# Sine_5KW_co_sac_copy.net
KiCad netlist of a schematic drawn in EAGLE
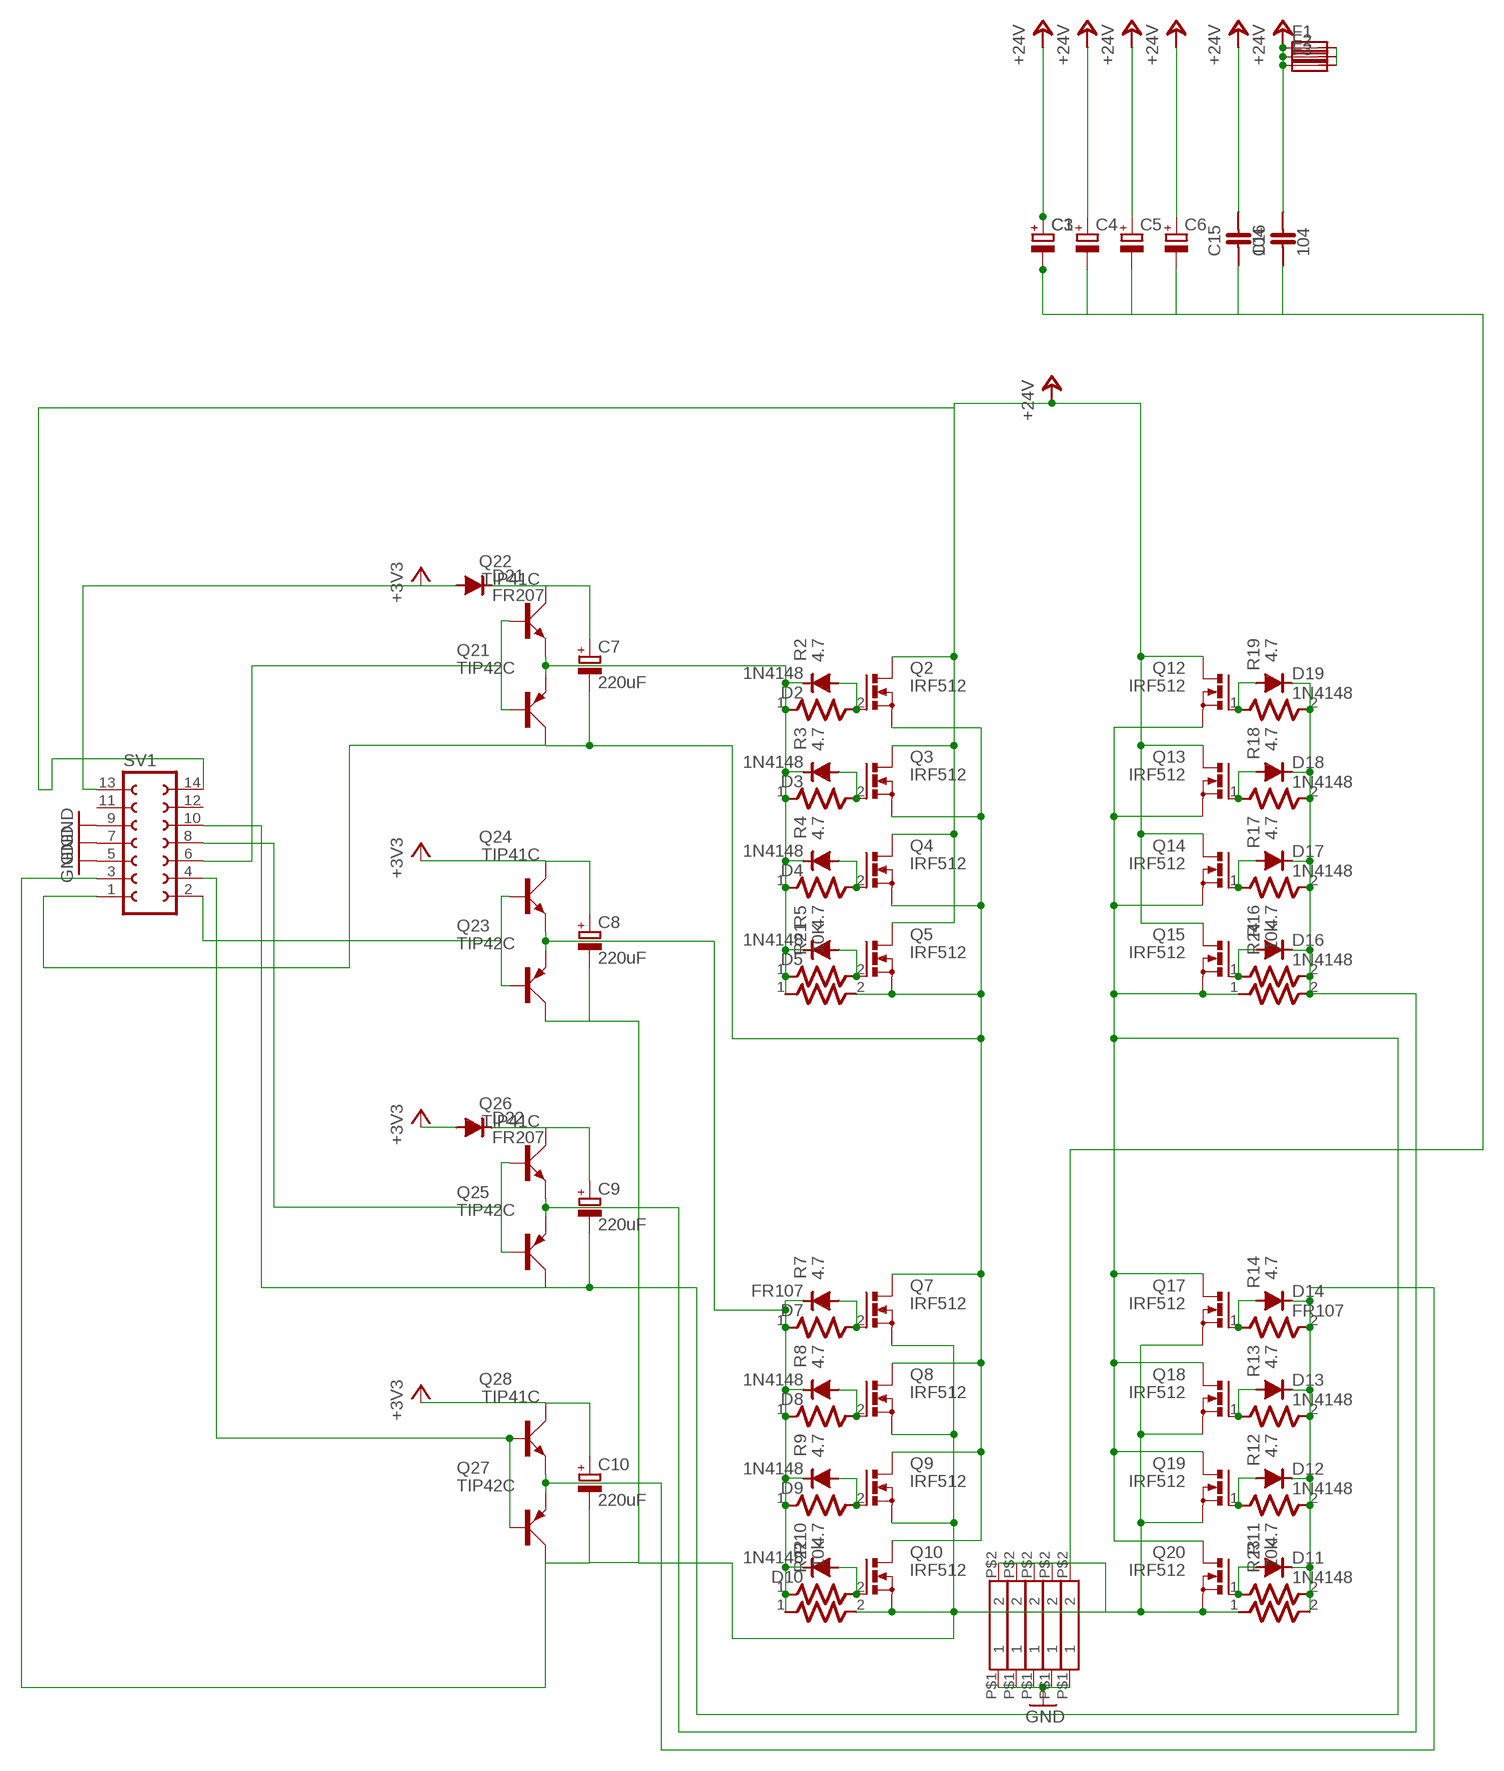
[diagram p0: schematic, sheet 1]

(export (version "E")
  (design (tool "Eeschema 10.0.6"))
  (components
    (comp (ref "C1")
      (value "CPOL-EUE7.5-18")
      (footprint "eagle-import:E7,5-18")
      (libsource (lib "eagle-import") (part "CPOL-EUE7.5-18"))
    )
    (comp (ref "C3")
      (value "CPOL-EUE7.5-18")
      (footprint "eagle-import:E7,5-18")
      (libsource (lib "eagle-import") (part "CPOL-EUE7.5-18"))
    )
    (comp (ref "C4")
      (value "CPOL-EUE7.5-18")
      (footprint "eagle-import:E7,5-18")
      (libsource (lib "eagle-import") (part "CPOL-EUE7.5-18"))
    )
    (comp (ref "C5")
      (value "CPOL-EUE7.5-18")
      (footprint "eagle-import:E7,5-18")
      (libsource (lib "eagle-import") (part "CPOL-EUE7.5-18"))
    )
    (comp (ref "C6")
      (value "CPOL-EUE7.5-18")
      (footprint "eagle-import:E7,5-18")
      (libsource (lib "eagle-import") (part "CPOL-EUE7.5-18"))
    )
    (comp (ref "C7")
      (value "220uF")
      (footprint "eagle-import:E5-8,5")
      (libsource (lib "eagle-import") (part "CPOL-EUE5-8.5"))
    )
    (comp (ref "C8")
      (value "220uF")
      (footprint "eagle-import:E5-8,5")
      (libsource (lib "eagle-import") (part "CPOL-EUE5-8.5"))
    )
    (comp (ref "C9")
      (value "220uF")
      (footprint "eagle-import:E5-8,5")
      (libsource (lib "eagle-import") (part "CPOL-EUE5-8.5"))
    )
    (comp (ref "C10")
      (value "220uF")
      (footprint "eagle-import:E5-8,5")
      (libsource (lib "eagle-import") (part "CPOL-EUE5-8.5"))
    )
    (comp (ref "C15")
      (value "104")
      (footprint "eagle-import:CAP-NP5")
      (libsource (lib "eagle-import") (part "CAP-NP5"))
    )
    (comp (ref "C16")
      (value "104")
      (footprint "eagle-import:CAP-NP5")
      (libsource (lib "eagle-import") (part "CAP-NP5"))
    )
    (comp (ref "D2")
      (value "1N4148")
      (footprint "eagle-import:D-7,5")
      (libsource (lib "eagle-import") (part "1N4148"))
    )
    (comp (ref "D3")
      (value "1N4148")
      (footprint "eagle-import:D-7,5")
      (libsource (lib "eagle-import") (part "1N4148"))
    )
    (comp (ref "D4")
      (value "1N4148")
      (footprint "eagle-import:D-7,5")
      (libsource (lib "eagle-import") (part "1N4148"))
    )
    (comp (ref "D5")
      (value "1N4148")
      (footprint "eagle-import:D-7,5")
      (libsource (lib "eagle-import") (part "1N4148"))
    )
    (comp (ref "D7")
      (value "FR107")
      (footprint "eagle-import:D-7,5")
      (libsource (lib "eagle-import") (part "1N4148"))
    )
    (comp (ref "D8")
      (value "1N4148")
      (footprint "eagle-import:D-7,5")
      (libsource (lib "eagle-import") (part "1N4148"))
    )
    (comp (ref "D9")
      (value "1N4148")
      (footprint "eagle-import:D-7,5")
      (libsource (lib "eagle-import") (part "1N4148"))
    )
    (comp (ref "D10")
      (value "1N4148")
      (footprint "eagle-import:D-7,5")
      (libsource (lib "eagle-import") (part "1N4148"))
    )
    (comp (ref "D11")
      (value "1N4148")
      (footprint "eagle-import:D-7,5")
      (libsource (lib "eagle-import") (part "1N4148"))
    )
    (comp (ref "D12")
      (value "1N4148")
      (footprint "eagle-import:D-7,5")
      (libsource (lib "eagle-import") (part "1N4148"))
    )
    (comp (ref "D13")
      (value "1N4148")
      (footprint "eagle-import:D-7,5")
      (libsource (lib "eagle-import") (part "1N4148"))
    )
    (comp (ref "D14")
      (value "FR107")
      (footprint "eagle-import:D-7,5")
      (libsource (lib "eagle-import") (part "1N4148"))
    )
    (comp (ref "D16")
      (value "1N4148")
      (footprint "eagle-import:D-7,5")
      (libsource (lib "eagle-import") (part "1N4148"))
    )
    (comp (ref "D17")
      (value "1N4148")
      (footprint "eagle-import:D-7,5")
      (libsource (lib "eagle-import") (part "1N4148"))
    )
    (comp (ref "D18")
      (value "1N4148")
      (footprint "eagle-import:D-7,5")
      (libsource (lib "eagle-import") (part "1N4148"))
    )
    (comp (ref "D19")
      (value "1N4148")
      (footprint "eagle-import:D-7,5")
      (libsource (lib "eagle-import") (part "1N4148"))
    )
    (comp (ref "D21")
      (value "FR207")
      (footprint "eagle-import:D-7,5")
      (libsource (lib "eagle-import") (part "1N4148"))
    )
    (comp (ref "D22")
      (value "FR207")
      (footprint "eagle-import:D-7,5")
      (libsource (lib "eagle-import") (part "1N4148"))
    )
    (comp (ref "F1")
      (value "LITTLEFUSE")
      (footprint "eagle-import:LITTLEFUSE")
      (libsource (lib "eagle-import") (part "LITTLEFUSE"))
    )
    (comp (ref "F2")
      (value "LITTLEFUSE")
      (footprint "eagle-import:LITTLEFUSE")
      (libsource (lib "eagle-import") (part "LITTLEFUSE"))
    )
    (comp (ref "F3")
      (value "LITTLEFUSE")
      (footprint "eagle-import:LITTLEFUSE")
      (libsource (lib "eagle-import") (part "LITTLEFUSE"))
    )
    (comp (ref "Q2")
      (value "IRF512")
      (footprint "eagle-import:TO220BV")
      (libsource (lib "eagle-import") (part "IRF512"))
    )
    (comp (ref "Q3")
      (value "IRF512")
      (footprint "eagle-import:TO220BV")
      (libsource (lib "eagle-import") (part "IRF512"))
    )
    (comp (ref "Q4")
      (value "IRF512")
      (footprint "eagle-import:TO220BV")
      (libsource (lib "eagle-import") (part "IRF512"))
    )
    (comp (ref "Q5")
      (value "IRF512")
      (footprint "eagle-import:TO220BV")
      (libsource (lib "eagle-import") (part "IRF512"))
    )
    (comp (ref "Q7")
      (value "IRF512")
      (footprint "eagle-import:TO220BV")
      (libsource (lib "eagle-import") (part "IRF512"))
    )
    (comp (ref "Q8")
      (value "IRF512")
      (footprint "eagle-import:TO220BV")
      (libsource (lib "eagle-import") (part "IRF512"))
    )
    (comp (ref "Q9")
      (value "IRF512")
      (footprint "eagle-import:TO220BV")
      (libsource (lib "eagle-import") (part "IRF512"))
    )
    (comp (ref "Q10")
      (value "IRF512")
      (footprint "eagle-import:TO220BV")
      (libsource (lib "eagle-import") (part "IRF512"))
    )
    (comp (ref "Q12")
      (value "IRF512")
      (footprint "eagle-import:TO220BV")
      (libsource (lib "eagle-import") (part "IRF512"))
    )
    (comp (ref "Q13")
      (value "IRF512")
      (footprint "eagle-import:TO220BV")
      (libsource (lib "eagle-import") (part "IRF512"))
    )
    (comp (ref "Q14")
      (value "IRF512")
      (footprint "eagle-import:TO220BV")
      (fields (field (name "SPICEPREFIX") "M"))
      (libsource (lib "eagle-import") (part "IRF512"))
    )
    (comp (ref "Q15")
      (value "IRF512")
      (footprint "eagle-import:TO220BV")
      (libsource (lib "eagle-import") (part "IRF512"))
    )
    (comp (ref "Q17")
      (value "IRF512")
      (footprint "eagle-import:TO220BV")
      (libsource (lib "eagle-import") (part "IRF512"))
    )
    (comp (ref "Q18")
      (value "IRF512")
      (footprint "eagle-import:TO220BV")
      (libsource (lib "eagle-import") (part "IRF512"))
    )
    (comp (ref "Q19")
      (value "IRF512")
      (footprint "eagle-import:TO220BV")
      (libsource (lib "eagle-import") (part "IRF512"))
    )
    (comp (ref "Q20")
      (value "IRF512")
      (footprint "eagle-import:TO220BV")
      (libsource (lib "eagle-import") (part "IRF512"))
    )
    (comp (ref "Q21")
      (value "TIP42C")
      (footprint "eagle-import:TO220AV")
      (fields (field (name "SPICEPREFIX") "Q"))
      (libsource (lib "eagle-import") (part "TIP42C"))
    )
    (comp (ref "Q22")
      (value "TIP41C")
      (footprint "eagle-import:TO220AV")
      (libsource (lib "eagle-import") (part "TIP41C"))
    )
    (comp (ref "Q23")
      (value "TIP42C")
      (footprint "eagle-import:TO220AV")
      (libsource (lib "eagle-import") (part "TIP42C"))
    )
    (comp (ref "Q24")
      (value "TIP41C")
      (footprint "eagle-import:TO220AV")
      (libsource (lib "eagle-import") (part "TIP41C"))
    )
    (comp (ref "Q25")
      (value "TIP42C")
      (footprint "eagle-import:TO220AV")
      (libsource (lib "eagle-import") (part "TIP42C"))
    )
    (comp (ref "Q26")
      (value "TIP41C")
      (footprint "eagle-import:TO220AV")
      (libsource (lib "eagle-import") (part "TIP41C"))
    )
    (comp (ref "Q27")
      (value "TIP42C")
      (footprint "eagle-import:TO220AV")
      (libsource (lib "eagle-import") (part "TIP42C"))
    )
    (comp (ref "Q28")
      (value "TIP41C")
      (footprint "eagle-import:TO220AV")
      (libsource (lib "eagle-import") (part "TIP41C"))
    )
    (comp (ref "R2")
      (value "4.7")
      (footprint "eagle-import:R-7,5")
      (libsource (lib "eagle-import") (part "R-7,5"))
    )
    (comp (ref "R3")
      (value "4.7")
      (footprint "eagle-import:R-7,5")
      (libsource (lib "eagle-import") (part "R-7,5"))
    )
    (comp (ref "R4")
      (value "4.7")
      (footprint "eagle-import:R-7,5")
      (libsource (lib "eagle-import") (part "R-7,5"))
    )
    (comp (ref "R5")
      (value "4.7")
      (footprint "eagle-import:R-7,5")
      (libsource (lib "eagle-import") (part "R-7,5"))
    )
    (comp (ref "R7")
      (value "4.7")
      (footprint "eagle-import:R-7,5")
      (libsource (lib "eagle-import") (part "R-7,5"))
    )
    (comp (ref "R8")
      (value "4.7")
      (footprint "eagle-import:R-7,5")
      (libsource (lib "eagle-import") (part "R-7,5"))
    )
    (comp (ref "R9")
      (value "4.7")
      (footprint "eagle-import:R-7,5")
      (libsource (lib "eagle-import") (part "R-7,5"))
    )
    (comp (ref "R10")
      (value "4.7")
      (footprint "eagle-import:R-7,5")
      (libsource (lib "eagle-import") (part "R-7,5"))
    )
    (comp (ref "R11")
      (value "4.7")
      (footprint "eagle-import:R-7,5")
      (libsource (lib "eagle-import") (part "R-7,5"))
    )
    (comp (ref "R12")
      (value "4.7")
      (footprint "eagle-import:R-7,5")
      (libsource (lib "eagle-import") (part "R-7,5"))
    )
    (comp (ref "R13")
      (value "4.7")
      (footprint "eagle-import:R-7,5")
      (libsource (lib "eagle-import") (part "R-7,5"))
    )
    (comp (ref "R14")
      (value "4.7")
      (footprint "eagle-import:R-7,5")
      (libsource (lib "eagle-import") (part "R-7,5"))
    )
    (comp (ref "R16")
      (value "4.7")
      (footprint "eagle-import:R-7,5")
      (libsource (lib "eagle-import") (part "R-7,5"))
    )
    (comp (ref "R17")
      (value "4.7")
      (footprint "eagle-import:R-7,5")
      (libsource (lib "eagle-import") (part "R-7,5"))
    )
    (comp (ref "R18")
      (value "4.7")
      (footprint "eagle-import:R-7,5")
      (libsource (lib "eagle-import") (part "R-7,5"))
    )
    (comp (ref "R19")
      (value "4.7")
      (footprint "eagle-import:R-7,5")
      (libsource (lib "eagle-import") (part "R-7,5"))
    )
    (comp (ref "R21")
      (value "10K")
      (footprint "eagle-import:R-7,5")
      (libsource (lib "eagle-import") (part "R-7,5"))
    )
    (comp (ref "R22")
      (value "10k")
      (footprint "eagle-import:R-7,5")
      (libsource (lib "eagle-import") (part "R-7,5"))
    )
    (comp (ref "R23")
      (value "10k")
      (footprint "eagle-import:R-7,5")
      (libsource (lib "eagle-import") (part "R-7,5"))
    )
    (comp (ref "R24")
      (value "10k")
      (footprint "eagle-import:R-7,5")
      (libsource (lib "eagle-import") (part "R-7,5"))
    )
    (comp (ref "SV1")
      (value "FE07-2")
      (footprint "eagle-import:FE07-2")
      (fields (field (name "SPICEPREFIX") "X"))
      (libsource (lib "eagle-import") (part "FE07-2"))
    )
    (comp (ref "U$2")
      (value "SHUNT")
      (footprint "eagle-import:SHUNT")
      (libsource (lib "eagle-import") (part "SHUNT"))
    )
    (comp (ref "U$3")
      (value "SHUNT")
      (footprint "eagle-import:SHUNT")
      (libsource (lib "eagle-import") (part "SHUNT"))
    )
    (comp (ref "U$8")
      (value "SHUNT")
      (footprint "eagle-import:SHUNT")
      (libsource (lib "eagle-import") (part "SHUNT"))
    )
    (comp (ref "U$9")
      (value "SHUNT")
      (footprint "eagle-import:SHUNT")
      (libsource (lib "eagle-import") (part "SHUNT"))
    )
    (comp (ref "U$10")
      (value "SHUNT")
      (footprint "eagle-import:SHUNT")
      (libsource (lib "eagle-import") (part "SHUNT"))
    )
  )
  (nets
    (net (code "1") (name "+3V3") (class "Default")
      (node (ref "C10") (pin "+") (pinfunction "+_+") (pintype "passive"))
      (node (ref "C8") (pin "+") (pinfunction "+_+") (pintype "passive"))
      (node (ref "D21") (pin "A") (pinfunction "A_A") (pintype "passive"))
      (node (ref "D22") (pin "A") (pinfunction "A_A") (pintype "passive"))
      (node (ref "Q24") (pin "C") (pinfunction "C_C") (pintype "passive"))
      (node (ref "Q28") (pin "C") (pinfunction "C_C") (pintype "passive"))
      (node (ref "SV1") (pin "13") (pinfunction "13_13") (pintype "passive"))
    )
    (net (code "2") (name "+24V") (class "Default")
      (node (ref "C1") (pin "+") (pinfunction "+_+") (pintype "passive"))
      (node (ref "C15") (pin "2") (pinfunction "2_2") (pintype "passive"))
      (node (ref "C16") (pin "2") (pinfunction "2_2") (pintype "passive"))
      (node (ref "C3") (pin "+") (pinfunction "+_+") (pintype "passive"))
      (node (ref "C4") (pin "+") (pinfunction "+_+") (pintype "passive"))
      (node (ref "C5") (pin "+") (pinfunction "+_+") (pintype "passive"))
      (node (ref "C6") (pin "+") (pinfunction "+_+") (pintype "passive"))
      (node (ref "F1") (pin "1") (pinfunction "1_1") (pintype "passive"))
      (node (ref "F2") (pin "1") (pinfunction "1_1") (pintype "passive"))
      (node (ref "F3") (pin "1") (pinfunction "1_1") (pintype "passive"))
      (node (ref "Q12") (pin "D") (pinfunction "D_D") (pintype "passive"))
      (node (ref "Q13") (pin "D") (pinfunction "D_D") (pintype "passive"))
      (node (ref "Q14") (pin "D") (pinfunction "D_D") (pintype "passive"))
      (node (ref "Q15") (pin "D") (pinfunction "D_D") (pintype "passive"))
      (node (ref "Q2") (pin "D") (pinfunction "D_D") (pintype "passive"))
      (node (ref "Q3") (pin "D") (pinfunction "D_D") (pintype "passive"))
      (node (ref "Q4") (pin "D") (pinfunction "D_D") (pintype "passive"))
      (node (ref "Q5") (pin "D") (pinfunction "D_D") (pintype "passive"))
      (node (ref "SV1") (pin "14") (pinfunction "14_14") (pintype "passive"))
    )
    (net (code "3") (name "GND") (class "Default")
      (node (ref "SV1") (pin "5") (pinfunction "5_5") (pintype "passive"))
      (node (ref "SV1") (pin "7") (pinfunction "7_7") (pintype "passive"))
      (node (ref "SV1") (pin "9") (pinfunction "9_9") (pintype "passive"))
      (node (ref "U$10") (pin "P$1") (pinfunction "1_P$1") (pintype "bidirectional"))
      (node (ref "U$2") (pin "P$1") (pinfunction "1_P$1") (pintype "bidirectional"))
      (node (ref "U$3") (pin "P$1") (pinfunction "1_P$1") (pintype "bidirectional"))
      (node (ref "U$8") (pin "P$1") (pinfunction "1_P$1") (pintype "bidirectional"))
      (node (ref "U$9") (pin "P$1") (pinfunction "1_P$1") (pintype "bidirectional"))
    )
    (net (code "4") (name "Net-(C7-Pad+)") (class "Default")
      (node (ref "C7") (pin "+") (pinfunction "+_+") (pintype "passive"))
      (node (ref "D21") (pin "C") (pinfunction "C_C") (pintype "passive"))
      (node (ref "Q22") (pin "C") (pinfunction "C_C") (pintype "passive"))
    )
    (net (code "5") (name "Net-(C7-Pad-)") (class "Default")
      (node (ref "C7") (pin "-") (pinfunction "-_-") (pintype "passive"))
      (node (ref "Q10") (pin "D") (pinfunction "D_D") (pintype "passive"))
      (node (ref "Q2") (pin "S") (pinfunction "S_S") (pintype "passive"))
      (node (ref "Q21") (pin "C") (pinfunction "C_C") (pintype "passive"))
      (node (ref "Q3") (pin "S") (pinfunction "S_S") (pintype "passive"))
      (node (ref "Q4") (pin "S") (pinfunction "S_S") (pintype "passive"))
      (node (ref "Q5") (pin "S") (pinfunction "S_S") (pintype "passive"))
      (node (ref "Q7") (pin "D") (pinfunction "D_D") (pintype "passive"))
      (node (ref "Q8") (pin "D") (pinfunction "D_D") (pintype "passive"))
      (node (ref "Q9") (pin "D") (pinfunction "D_D") (pintype "passive"))
      (node (ref "R21") (pin "2") (pinfunction "2_2") (pintype "passive"))
      (node (ref "SV1") (pin "1") (pinfunction "1_1") (pintype "passive"))
    )
    (net (code "6") (name "Net-(C9-Pad+)") (class "Default")
      (node (ref "C9") (pin "+") (pinfunction "+_+") (pintype "passive"))
      (node (ref "D22") (pin "C") (pinfunction "C_C") (pintype "passive"))
      (node (ref "Q26") (pin "C") (pinfunction "C_C") (pintype "passive"))
    )
    (net (code "7") (name "Net-(C9-Pad-)") (class "Default")
      (node (ref "C9") (pin "-") (pinfunction "-_-") (pintype "passive"))
      (node (ref "Q12") (pin "S") (pinfunction "S_S") (pintype "passive"))
      (node (ref "Q13") (pin "S") (pinfunction "S_S") (pintype "passive"))
      (node (ref "Q14") (pin "S") (pinfunction "S_S") (pintype "passive"))
      (node (ref "Q15") (pin "S") (pinfunction "S_S") (pintype "passive"))
      (node (ref "Q17") (pin "D") (pinfunction "D_D") (pintype "passive"))
      (node (ref "Q18") (pin "D") (pinfunction "D_D") (pintype "passive"))
      (node (ref "Q19") (pin "D") (pinfunction "D_D") (pintype "passive"))
      (node (ref "Q20") (pin "D") (pinfunction "D_D") (pintype "passive"))
      (node (ref "Q25") (pin "C") (pinfunction "C_C") (pintype "passive"))
      (node (ref "R24") (pin "1") (pinfunction "1_1") (pintype "passive"))
      (node (ref "SV1") (pin "10") (pinfunction "10_10") (pintype "passive"))
    )
    (net (code "8") (name "Net-(D2-PadA)") (class "Default")
      (node (ref "D2") (pin "A") (pinfunction "A_A") (pintype "passive"))
      (node (ref "Q2") (pin "G") (pinfunction "G_G") (pintype "passive"))
      (node (ref "R2") (pin "2") (pinfunction "2_2") (pintype "passive"))
    )
    (net (code "9") (name "Net-(D2-PadC)") (class "Default")
      (node (ref "D2") (pin "C") (pinfunction "C_C") (pintype "passive"))
      (node (ref "D3") (pin "C") (pinfunction "C_C") (pintype "passive"))
      (node (ref "D4") (pin "C") (pinfunction "C_C") (pintype "passive"))
      (node (ref "D5") (pin "C") (pinfunction "C_C") (pintype "passive"))
      (node (ref "Q21") (pin "E") (pinfunction "E_E") (pintype "passive"))
      (node (ref "Q22") (pin "E") (pinfunction "E_E") (pintype "passive"))
      (node (ref "R2") (pin "1") (pinfunction "1_1") (pintype "passive"))
      (node (ref "R21") (pin "1") (pinfunction "1_1") (pintype "passive"))
      (node (ref "R3") (pin "1") (pinfunction "1_1") (pintype "passive"))
      (node (ref "R4") (pin "1") (pinfunction "1_1") (pintype "passive"))
      (node (ref "R5") (pin "1") (pinfunction "1_1") (pintype "passive"))
    )
    (net (code "10") (name "Net-(D3-PadA)") (class "Default")
      (node (ref "D3") (pin "A") (pinfunction "A_A") (pintype "passive"))
      (node (ref "Q3") (pin "G") (pinfunction "G_G") (pintype "passive"))
      (node (ref "R3") (pin "2") (pinfunction "2_2") (pintype "passive"))
    )
    (net (code "11") (name "Net-(D4-PadA)") (class "Default")
      (node (ref "D4") (pin "A") (pinfunction "A_A") (pintype "passive"))
      (node (ref "Q4") (pin "G") (pinfunction "G_G") (pintype "passive"))
      (node (ref "R4") (pin "2") (pinfunction "2_2") (pintype "passive"))
    )
    (net (code "12") (name "Net-(D5-PadA)") (class "Default")
      (node (ref "D5") (pin "A") (pinfunction "A_A") (pintype "passive"))
      (node (ref "Q5") (pin "G") (pinfunction "G_G") (pintype "passive"))
      (node (ref "R5") (pin "2") (pinfunction "2_2") (pintype "passive"))
    )
    (net (code "13") (name "Net-(D7-PadA)") (class "Default")
      (node (ref "D7") (pin "A") (pinfunction "A_A") (pintype "passive"))
      (node (ref "Q7") (pin "G") (pinfunction "G_G") (pintype "passive"))
      (node (ref "R7") (pin "2") (pinfunction "2_2") (pintype "passive"))
    )
    (net (code "14") (name "Net-(D8-PadA)") (class "Default")
      (node (ref "D8") (pin "A") (pinfunction "A_A") (pintype "passive"))
      (node (ref "Q8") (pin "G") (pinfunction "G_G") (pintype "passive"))
      (node (ref "R8") (pin "2") (pinfunction "2_2") (pintype "passive"))
    )
    (net (code "15") (name "Net-(D9-PadA)") (class "Default")
      (node (ref "D9") (pin "A") (pinfunction "A_A") (pintype "passive"))
      (node (ref "Q9") (pin "G") (pinfunction "G_G") (pintype "passive"))
      (node (ref "R9") (pin "2") (pinfunction "2_2") (pintype "passive"))
    )
    (net (code "16") (name "Net-(D10-PadA)") (class "Default")
      (node (ref "D10") (pin "A") (pinfunction "A_A") (pintype "passive"))
      (node (ref "Q10") (pin "G") (pinfunction "G_G") (pintype "passive"))
      (node (ref "R10") (pin "2") (pinfunction "2_2") (pintype "passive"))
    )
    (net (code "17") (name "Net-(D10-PadC)") (class "Default")
      (node (ref "D10") (pin "C") (pinfunction "C_C") (pintype "passive"))
      (node (ref "D7") (pin "C") (pinfunction "C_C") (pintype "passive"))
      (node (ref "D8") (pin "C") (pinfunction "C_C") (pintype "passive"))
      (node (ref "D9") (pin "C") (pinfunction "C_C") (pintype "passive"))
      (node (ref "Q23") (pin "E") (pinfunction "E_E") (pintype "passive"))
      (node (ref "Q24") (pin "E") (pinfunction "E_E") (pintype "passive"))
      (node (ref "R10") (pin "1") (pinfunction "1_1") (pintype "passive"))
      (node (ref "R22") (pin "1") (pinfunction "1_1") (pintype "passive"))
      (node (ref "R7") (pin "1") (pinfunction "1_1") (pintype "passive"))
      (node (ref "R8") (pin "1") (pinfunction "1_1") (pintype "passive"))
      (node (ref "R9") (pin "1") (pinfunction "1_1") (pintype "passive"))
    )
    (net (code "18") (name "Net-(D11-PadA)") (class "Default")
      (node (ref "D11") (pin "A") (pinfunction "A_A") (pintype "passive"))
      (node (ref "Q20") (pin "G") (pinfunction "G_G") (pintype "passive"))
      (node (ref "R11") (pin "1") (pinfunction "1_1") (pintype "passive"))
    )
    (net (code "19") (name "Net-(D11-PadC)") (class "Default")
      (node (ref "D11") (pin "C") (pinfunction "C_C") (pintype "passive"))
      (node (ref "D12") (pin "C") (pinfunction "C_C") (pintype "passive"))
      (node (ref "D13") (pin "C") (pinfunction "C_C") (pintype "passive"))
      (node (ref "D14") (pin "C") (pinfunction "C_C") (pintype "passive"))
      (node (ref "Q27") (pin "E") (pinfunction "E_E") (pintype "passive"))
      (node (ref "Q28") (pin "E") (pinfunction "E_E") (pintype "passive"))
      (node (ref "R11") (pin "2") (pinfunction "2_2") (pintype "passive"))
      (node (ref "R12") (pin "2") (pinfunction "2_2") (pintype "passive"))
      (node (ref "R13") (pin "2") (pinfunction "2_2") (pintype "passive"))
      (node (ref "R14") (pin "2") (pinfunction "2_2") (pintype "passive"))
      (node (ref "R23") (pin "2") (pinfunction "2_2") (pintype "passive"))
    )
    (net (code "20") (name "Net-(D12-PadA)") (class "Default")
      (node (ref "D12") (pin "A") (pinfunction "A_A") (pintype "passive"))
      (node (ref "Q19") (pin "G") (pinfunction "G_G") (pintype "passive"))
      (node (ref "R12") (pin "1") (pinfunction "1_1") (pintype "passive"))
    )
    (net (code "21") (name "Net-(D13-PadA)") (class "Default")
      (node (ref "D13") (pin "A") (pinfunction "A_A") (pintype "passive"))
      (node (ref "Q18") (pin "G") (pinfunction "G_G") (pintype "passive"))
      (node (ref "R13") (pin "1") (pinfunction "1_1") (pintype "passive"))
    )
    (net (code "22") (name "Net-(D14-PadA)") (class "Default")
      (node (ref "D14") (pin "A") (pinfunction "A_A") (pintype "passive"))
      (node (ref "Q17") (pin "G") (pinfunction "G_G") (pintype "passive"))
      (node (ref "R14") (pin "1") (pinfunction "1_1") (pintype "passive"))
    )
    (net (code "23") (name "Net-(D16-PadA)") (class "Default")
      (node (ref "D16") (pin "A") (pinfunction "A_A") (pintype "passive"))
      (node (ref "Q15") (pin "G") (pinfunction "G_G") (pintype "passive"))
      (node (ref "R16") (pin "1") (pinfunction "1_1") (pintype "passive"))
    )
    (net (code "24") (name "Net-(D16-PadC)") (class "Default")
      (node (ref "D16") (pin "C") (pinfunction "C_C") (pintype "passive"))
      (node (ref "D17") (pin "C") (pinfunction "C_C") (pintype "passive"))
      (node (ref "D18") (pin "C") (pinfunction "C_C") (pintype "passive"))
      (node (ref "D19") (pin "C") (pinfunction "C_C") (pintype "passive"))
      (node (ref "Q25") (pin "E") (pinfunction "E_E") (pintype "passive"))
      (node (ref "Q26") (pin "E") (pinfunction "E_E") (pintype "passive"))
      (node (ref "R16") (pin "2") (pinfunction "2_2") (pintype "passive"))
      (node (ref "R17") (pin "2") (pinfunction "2_2") (pintype "passive"))
      (node (ref "R18") (pin "2") (pinfunction "2_2") (pintype "passive"))
      (node (ref "R19") (pin "2") (pinfunction "2_2") (pintype "passive"))
      (node (ref "R24") (pin "2") (pinfunction "2_2") (pintype "passive"))
    )
    (net (code "25") (name "Net-(D17-PadA)") (class "Default")
      (node (ref "D17") (pin "A") (pinfunction "A_A") (pintype "passive"))
      (node (ref "Q14") (pin "G") (pinfunction "G_G") (pintype "passive"))
      (node (ref "R17") (pin "1") (pinfunction "1_1") (pintype "passive"))
    )
    (net (code "26") (name "Net-(D18-PadA)") (class "Default")
      (node (ref "D18") (pin "A") (pinfunction "A_A") (pintype "passive"))
      (node (ref "Q13") (pin "G") (pinfunction "G_G") (pintype "passive"))
      (node (ref "R18") (pin "1") (pinfunction "1_1") (pintype "passive"))
    )
    (net (code "27") (name "Net-(D19-PadA)") (class "Default")
      (node (ref "D19") (pin "A") (pinfunction "A_A") (pintype "passive"))
      (node (ref "Q12") (pin "G") (pinfunction "G_G") (pintype "passive"))
      (node (ref "R19") (pin "1") (pinfunction "1_1") (pintype "passive"))
    )
    (net (code "28") (name "Net-(F1-Pad2)") (class "Default")
      (node (ref "F1") (pin "2") (pinfunction "2_2") (pintype "passive"))
      (node (ref "F2") (pin "2") (pinfunction "2_2") (pintype "passive"))
      (node (ref "F3") (pin "2") (pinfunction "2_2") (pintype "passive"))
    )
    (net (code "29") (name "Net-(Q21-PadB)") (class "Default")
      (node (ref "Q21") (pin "B") (pinfunction "B_B") (pintype "passive"))
      (node (ref "Q22") (pin "B") (pinfunction "B_B") (pintype "passive"))
      (node (ref "SV1") (pin "6") (pinfunction "6_6") (pintype "passive"))
    )
    (net (code "30") (name "Net-(Q23-PadB)") (class "Default")
      (node (ref "Q23") (pin "B") (pinfunction "B_B") (pintype "passive"))
      (node (ref "Q24") (pin "B") (pinfunction "B_B") (pintype "passive"))
      (node (ref "SV1") (pin "2") (pinfunction "2_2") (pintype "passive"))
    )
    (net (code "31") (name "Net-(Q25-PadB)") (class "Default")
      (node (ref "Q25") (pin "B") (pinfunction "B_B") (pintype "passive"))
      (node (ref "Q26") (pin "B") (pinfunction "B_B") (pintype "passive"))
      (node (ref "SV1") (pin "8") (pinfunction "8_8") (pintype "passive"))
    )
    (net (code "32") (name "Net-(Q27-PadB)") (class "Default")
      (node (ref "Q27") (pin "B") (pinfunction "B_B") (pintype "passive"))
      (node (ref "Q28") (pin "B") (pinfunction "B_B") (pintype "passive"))
      (node (ref "SV1") (pin "4") (pinfunction "4_4") (pintype "passive"))
    )
    (net (code "33") (name "Net-(U$10-2)") (class "Default")
      (node (ref "C1") (pin "-") (pinfunction "-_-") (pintype "passive"))
      (node (ref "C10") (pin "-") (pinfunction "-_-") (pintype "passive"))
      (node (ref "C15") (pin "1") (pinfunction "1_1") (pintype "passive"))
      (node (ref "C16") (pin "1") (pinfunction "1_1") (pintype "passive"))
      (node (ref "C3") (pin "-") (pinfunction "-_-") (pintype "passive"))
      (node (ref "C4") (pin "-") (pinfunction "-_-") (pintype "passive"))
      (node (ref "C5") (pin "-") (pinfunction "-_-") (pintype "passive"))
      (node (ref "C6") (pin "-") (pinfunction "-_-") (pintype "passive"))
      (node (ref "C8") (pin "-") (pinfunction "-_-") (pintype "passive"))
      (node (ref "Q10") (pin "S") (pinfunction "S_S") (pintype "passive"))
      (node (ref "Q17") (pin "S") (pinfunction "S_S") (pintype "passive"))
      (node (ref "Q18") (pin "S") (pinfunction "S_S") (pintype "passive"))
      (node (ref "Q19") (pin "S") (pinfunction "S_S") (pintype "passive"))
      (node (ref "Q20") (pin "S") (pinfunction "S_S") (pintype "passive"))
      (node (ref "Q23") (pin "C") (pinfunction "C_C") (pintype "passive"))
      (node (ref "Q27") (pin "C") (pinfunction "C_C") (pintype "passive"))
      (node (ref "Q7") (pin "S") (pinfunction "S_S") (pintype "passive"))
      (node (ref "Q8") (pin "S") (pinfunction "S_S") (pintype "passive"))
      (node (ref "Q9") (pin "S") (pinfunction "S_S") (pintype "passive"))
      (node (ref "R22") (pin "2") (pinfunction "2_2") (pintype "passive"))
      (node (ref "R23") (pin "1") (pinfunction "1_1") (pintype "passive"))
      (node (ref "SV1") (pin "3") (pinfunction "3_3") (pintype "passive"))
      (node (ref "U$10") (pin "P$2") (pinfunction "2_P$2") (pintype "bidirectional"))
      (node (ref "U$2") (pin "P$2") (pinfunction "2_P$2") (pintype "bidirectional"))
      (node (ref "U$3") (pin "P$2") (pinfunction "2_P$2") (pintype "bidirectional"))
      (node (ref "U$8") (pin "P$2") (pinfunction "2_P$2") (pintype "bidirectional"))
      (node (ref "U$9") (pin "P$2") (pinfunction "2_P$2") (pintype "bidirectional"))
    )
    (net (code "34") (name "unconnected-(SV1-Pad11)") (class "Default")
      (node (ref "SV1") (pin "11") (pinfunction "11_11") (pintype "passive"))
    )
    (net (code "35") (name "unconnected-(SV1-Pad12)") (class "Default")
      (node (ref "SV1") (pin "12") (pinfunction "12_12") (pintype "passive"))
    )
  )
)
